# led7.net
KiCad netlist of a schematic drawn in Altium Designer
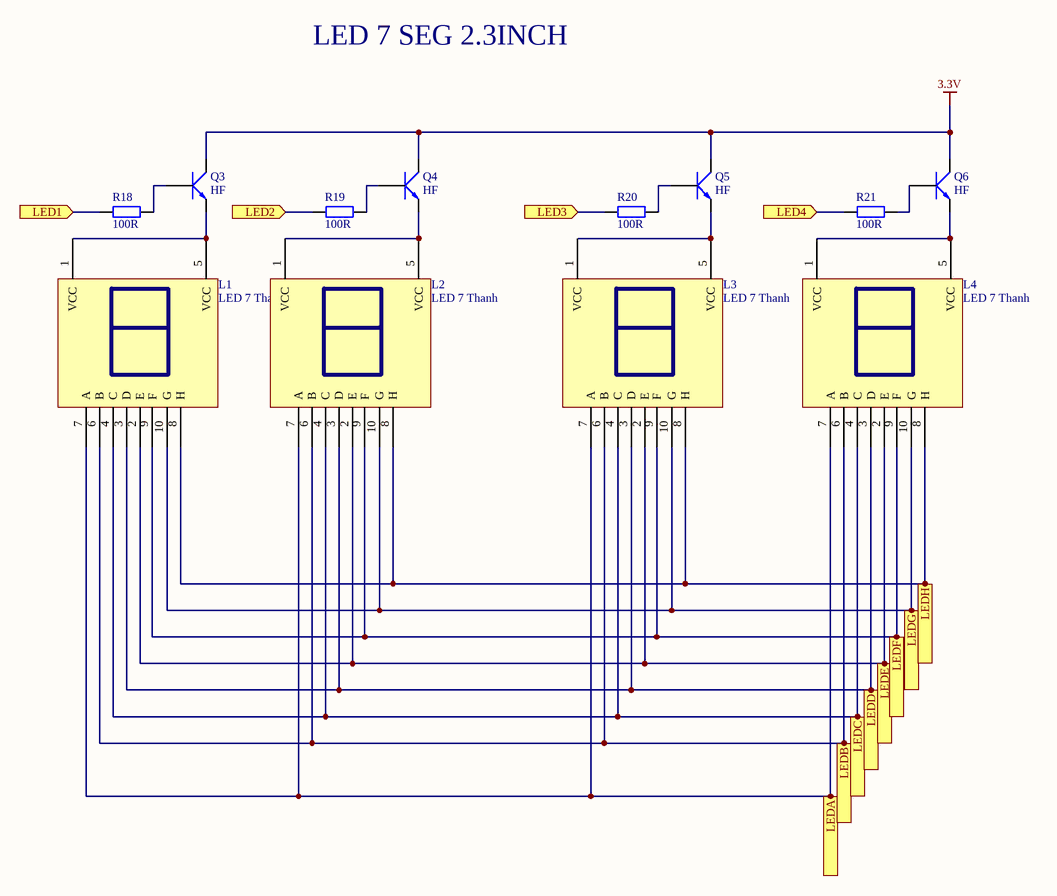
[diagram p0: led7.SchDoc]

(export (version "E")
  (design (tool "Eeschema 10.0.6"))
  (components
    (comp (ref "L1")
      (value "LED 7 Thanh")
      (footprint "LED7SEG_2.3inch")
      (description "Dán")
      (libsource (lib "Altium_Lib_by_KhueNguyenCreator") (part "LED 7x1 2.3inch Anot"))
    )
    (comp (ref "L2")
      (value "LED 7 Thanh")
      (footprint "LED7SEG_2.3inch")
      (description "Dán")
      (libsource (lib "Altium_Lib_by_KhueNguyenCreator") (part "LED 7x1 2.3inch Anot"))
    )
    (comp (ref "L3")
      (value "LED 7 Thanh")
      (footprint "LED7SEG_2.3inch")
      (description "Dán")
      (libsource (lib "Altium_Lib_by_KhueNguyenCreator") (part "LED 7x1 2.3inch Anot"))
    )
    (comp (ref "L4")
      (value "LED 7 Thanh")
      (footprint "LED7SEG_2.3inch")
      (description "Dán")
      (libsource (lib "Altium_Lib_by_KhueNguyenCreator") (part "LED 7x1 2.3inch Anot"))
    )
    (comp (ref "Q3")
      (value "HF")
      (footprint "SOT23")
      (description "NPN transistor")
      (libsource (lib "Altium_Lib_by_KhueNguyenCreator") (part "C1815 HF SMD"))
    )
    (comp (ref "Q4")
      (value "HF")
      (footprint "SOT23")
      (description "NPN transistor")
      (libsource (lib "Altium_Lib_by_KhueNguyenCreator") (part "C1815 HF SMD"))
    )
    (comp (ref "Q5")
      (value "HF")
      (footprint "SOT23")
      (description "NPN transistor")
      (libsource (lib "Altium_Lib_by_KhueNguyenCreator") (part "C1815 HF SMD"))
    )
    (comp (ref "Q6")
      (value "HF")
      (footprint "SOT23")
      (description "NPN transistor")
      (libsource (lib "Altium_Lib_by_KhueNguyenCreator") (part "C1815 HF SMD"))
    )
    (comp (ref "R18")
      (value "100R")
      (footprint "tro smd 0805")
      (description "Dán")
      (libsource (lib "Altium_Lib_by_KhueNguyenCreator") (part "Tro 0805 5% 100R"))
    )
    (comp (ref "R19")
      (value "100R")
      (footprint "tro smd 0805")
      (description "Dán")
      (libsource (lib "Altium_Lib_by_KhueNguyenCreator") (part "Tro 0805 5% 100R"))
    )
    (comp (ref "R20")
      (value "100R")
      (footprint "tro smd 0805")
      (description "Dán")
      (libsource (lib "Altium_Lib_by_KhueNguyenCreator") (part "Tro 0805 5% 100R"))
    )
    (comp (ref "R21")
      (value "100R")
      (footprint "tro smd 0805")
      (description "Dán")
      (libsource (lib "Altium_Lib_by_KhueNguyenCreator") (part "Tro 0805 5% 100R"))
    )
  )
  (nets
    (net (code "1") (name "/LED1") (class "Default")
      (node (ref "R18") (pin "1") (pinfunction "1_1") (pintype "passive"))
    )
    (net (code "2") (name "/LED2") (class "Default")
      (node (ref "R19") (pin "1") (pinfunction "1_1") (pintype "passive"))
    )
    (net (code "3") (name "/LED3") (class "Default")
      (node (ref "R20") (pin "1") (pinfunction "1_1") (pintype "passive"))
    )
    (net (code "4") (name "/LED4") (class "Default")
      (node (ref "R21") (pin "1") (pinfunction "1_1") (pintype "passive"))
    )
    (net (code "5") (name "/LEDA") (class "Default")
      (node (ref "L1") (pin "7") (pinfunction "A_7") (pintype "passive"))
      (node (ref "L2") (pin "7") (pinfunction "A_7") (pintype "passive"))
      (node (ref "L3") (pin "7") (pinfunction "A_7") (pintype "passive"))
      (node (ref "L4") (pin "7") (pinfunction "A_7") (pintype "passive"))
    )
    (net (code "6") (name "/LEDB") (class "Default")
      (node (ref "L1") (pin "6") (pinfunction "B_6") (pintype "passive"))
      (node (ref "L2") (pin "6") (pinfunction "B_6") (pintype "passive"))
      (node (ref "L3") (pin "6") (pinfunction "B_6") (pintype "passive"))
      (node (ref "L4") (pin "6") (pinfunction "B_6") (pintype "passive"))
    )
    (net (code "7") (name "/LEDC") (class "Default")
      (node (ref "L1") (pin "4") (pinfunction "C_4") (pintype "passive"))
      (node (ref "L2") (pin "4") (pinfunction "C_4") (pintype "passive"))
      (node (ref "L3") (pin "4") (pinfunction "C_4") (pintype "passive"))
      (node (ref "L4") (pin "4") (pinfunction "C_4") (pintype "passive"))
    )
    (net (code "8") (name "/LEDD") (class "Default")
      (node (ref "L1") (pin "3") (pinfunction "D_3") (pintype "passive"))
      (node (ref "L2") (pin "3") (pinfunction "D_3") (pintype "passive"))
      (node (ref "L3") (pin "3") (pinfunction "D_3") (pintype "passive"))
      (node (ref "L4") (pin "3") (pinfunction "D_3") (pintype "passive"))
    )
    (net (code "9") (name "/LEDE") (class "Default")
      (node (ref "L1") (pin "2") (pinfunction "E_2") (pintype "passive"))
      (node (ref "L2") (pin "2") (pinfunction "E_2") (pintype "passive"))
      (node (ref "L3") (pin "2") (pinfunction "E_2") (pintype "passive"))
      (node (ref "L4") (pin "2") (pinfunction "E_2") (pintype "passive"))
    )
    (net (code "10") (name "/LEDF") (class "Default")
      (node (ref "L1") (pin "9") (pinfunction "F_9") (pintype "passive"))
      (node (ref "L2") (pin "9") (pinfunction "F_9") (pintype "passive"))
      (node (ref "L3") (pin "9") (pinfunction "F_9") (pintype "passive"))
      (node (ref "L4") (pin "9") (pinfunction "F_9") (pintype "passive"))
    )
    (net (code "11") (name "/LEDG") (class "Default")
      (node (ref "L1") (pin "10") (pinfunction "G_10") (pintype "passive"))
      (node (ref "L2") (pin "10") (pinfunction "G_10") (pintype "passive"))
      (node (ref "L3") (pin "10") (pinfunction "G_10") (pintype "passive"))
      (node (ref "L4") (pin "10") (pinfunction "G_10") (pintype "passive"))
    )
    (net (code "12") (name "/LEDH") (class "Default")
      (node (ref "L1") (pin "8") (pinfunction "H_8") (pintype "passive"))
      (node (ref "L2") (pin "8") (pinfunction "H_8") (pintype "passive"))
      (node (ref "L3") (pin "8") (pinfunction "H_8") (pintype "passive"))
      (node (ref "L4") (pin "8") (pinfunction "H_8") (pintype "passive"))
    )
    (net (code "13") (name "3.3V") (class "Default")
      (node (ref "Q3") (pin "3") (pinfunction "C_3") (pintype "passive"))
      (node (ref "Q4") (pin "3") (pinfunction "C_3") (pintype "passive"))
      (node (ref "Q5") (pin "3") (pinfunction "C_3") (pintype "passive"))
      (node (ref "Q6") (pin "3") (pinfunction "C_3") (pintype "passive"))
    )
    (net (code "14") (name "Net-(Q3-B)") (class "Default")
      (node (ref "Q3") (pin "1") (pinfunction "B_1") (pintype "passive"))
      (node (ref "R18") (pin "2") (pinfunction "2_2") (pintype "passive"))
    )
    (net (code "15") (name "Net-(Q3-E)") (class "Default")
      (node (ref "L1") (pin "5") (pinfunction "VCC_5") (pintype "passive"))
      (node (ref "Q3") (pin "2") (pinfunction "E_2") (pintype "passive"))
    )
    (net (code "16") (name "Net-(Q4-B)") (class "Default")
      (node (ref "Q4") (pin "1") (pinfunction "B_1") (pintype "passive"))
      (node (ref "R19") (pin "2") (pinfunction "2_2") (pintype "passive"))
    )
    (net (code "17") (name "Net-(Q4-E)") (class "Default")
      (node (ref "L2") (pin "5") (pinfunction "VCC_5") (pintype "passive"))
      (node (ref "Q4") (pin "2") (pinfunction "E_2") (pintype "passive"))
    )
    (net (code "18") (name "Net-(Q5-B)") (class "Default")
      (node (ref "Q5") (pin "1") (pinfunction "B_1") (pintype "passive"))
      (node (ref "R20") (pin "2") (pinfunction "2_2") (pintype "passive"))
    )
    (net (code "19") (name "Net-(Q5-E)") (class "Default")
      (node (ref "L3") (pin "5") (pinfunction "VCC_5") (pintype "passive"))
      (node (ref "Q5") (pin "2") (pinfunction "E_2") (pintype "passive"))
    )
    (net (code "20") (name "Net-(Q6-B)") (class "Default")
      (node (ref "Q6") (pin "1") (pinfunction "B_1") (pintype "passive"))
      (node (ref "R21") (pin "2") (pinfunction "2_2") (pintype "passive"))
    )
    (net (code "21") (name "Net-(Q6-E)") (class "Default")
      (node (ref "L4") (pin "1") (pinfunction "VCC_1") (pintype "passive"))
      (node (ref "L4") (pin "5") (pinfunction "VCC_5") (pintype "passive"))
      (node (ref "Q6") (pin "2") (pinfunction "E_2") (pintype "passive"))
    )
    (net (code "22") (name "unconnected-(L1-VCC-Pad1)") (class "Default")
      (node (ref "L1") (pin "1") (pinfunction "VCC_1") (pintype "passive"))
    )
    (net (code "23") (name "unconnected-(L2-VCC-Pad1)") (class "Default")
      (node (ref "L2") (pin "1") (pinfunction "VCC_1") (pintype "passive"))
    )
    (net (code "24") (name "unconnected-(L3-VCC-Pad1)") (class "Default")
      (node (ref "L3") (pin "1") (pinfunction "VCC_1") (pintype "passive"))
    )
  )
)
